# Vesta_cape.net
KiCad netlist of a schematic drawn in Altium Designer
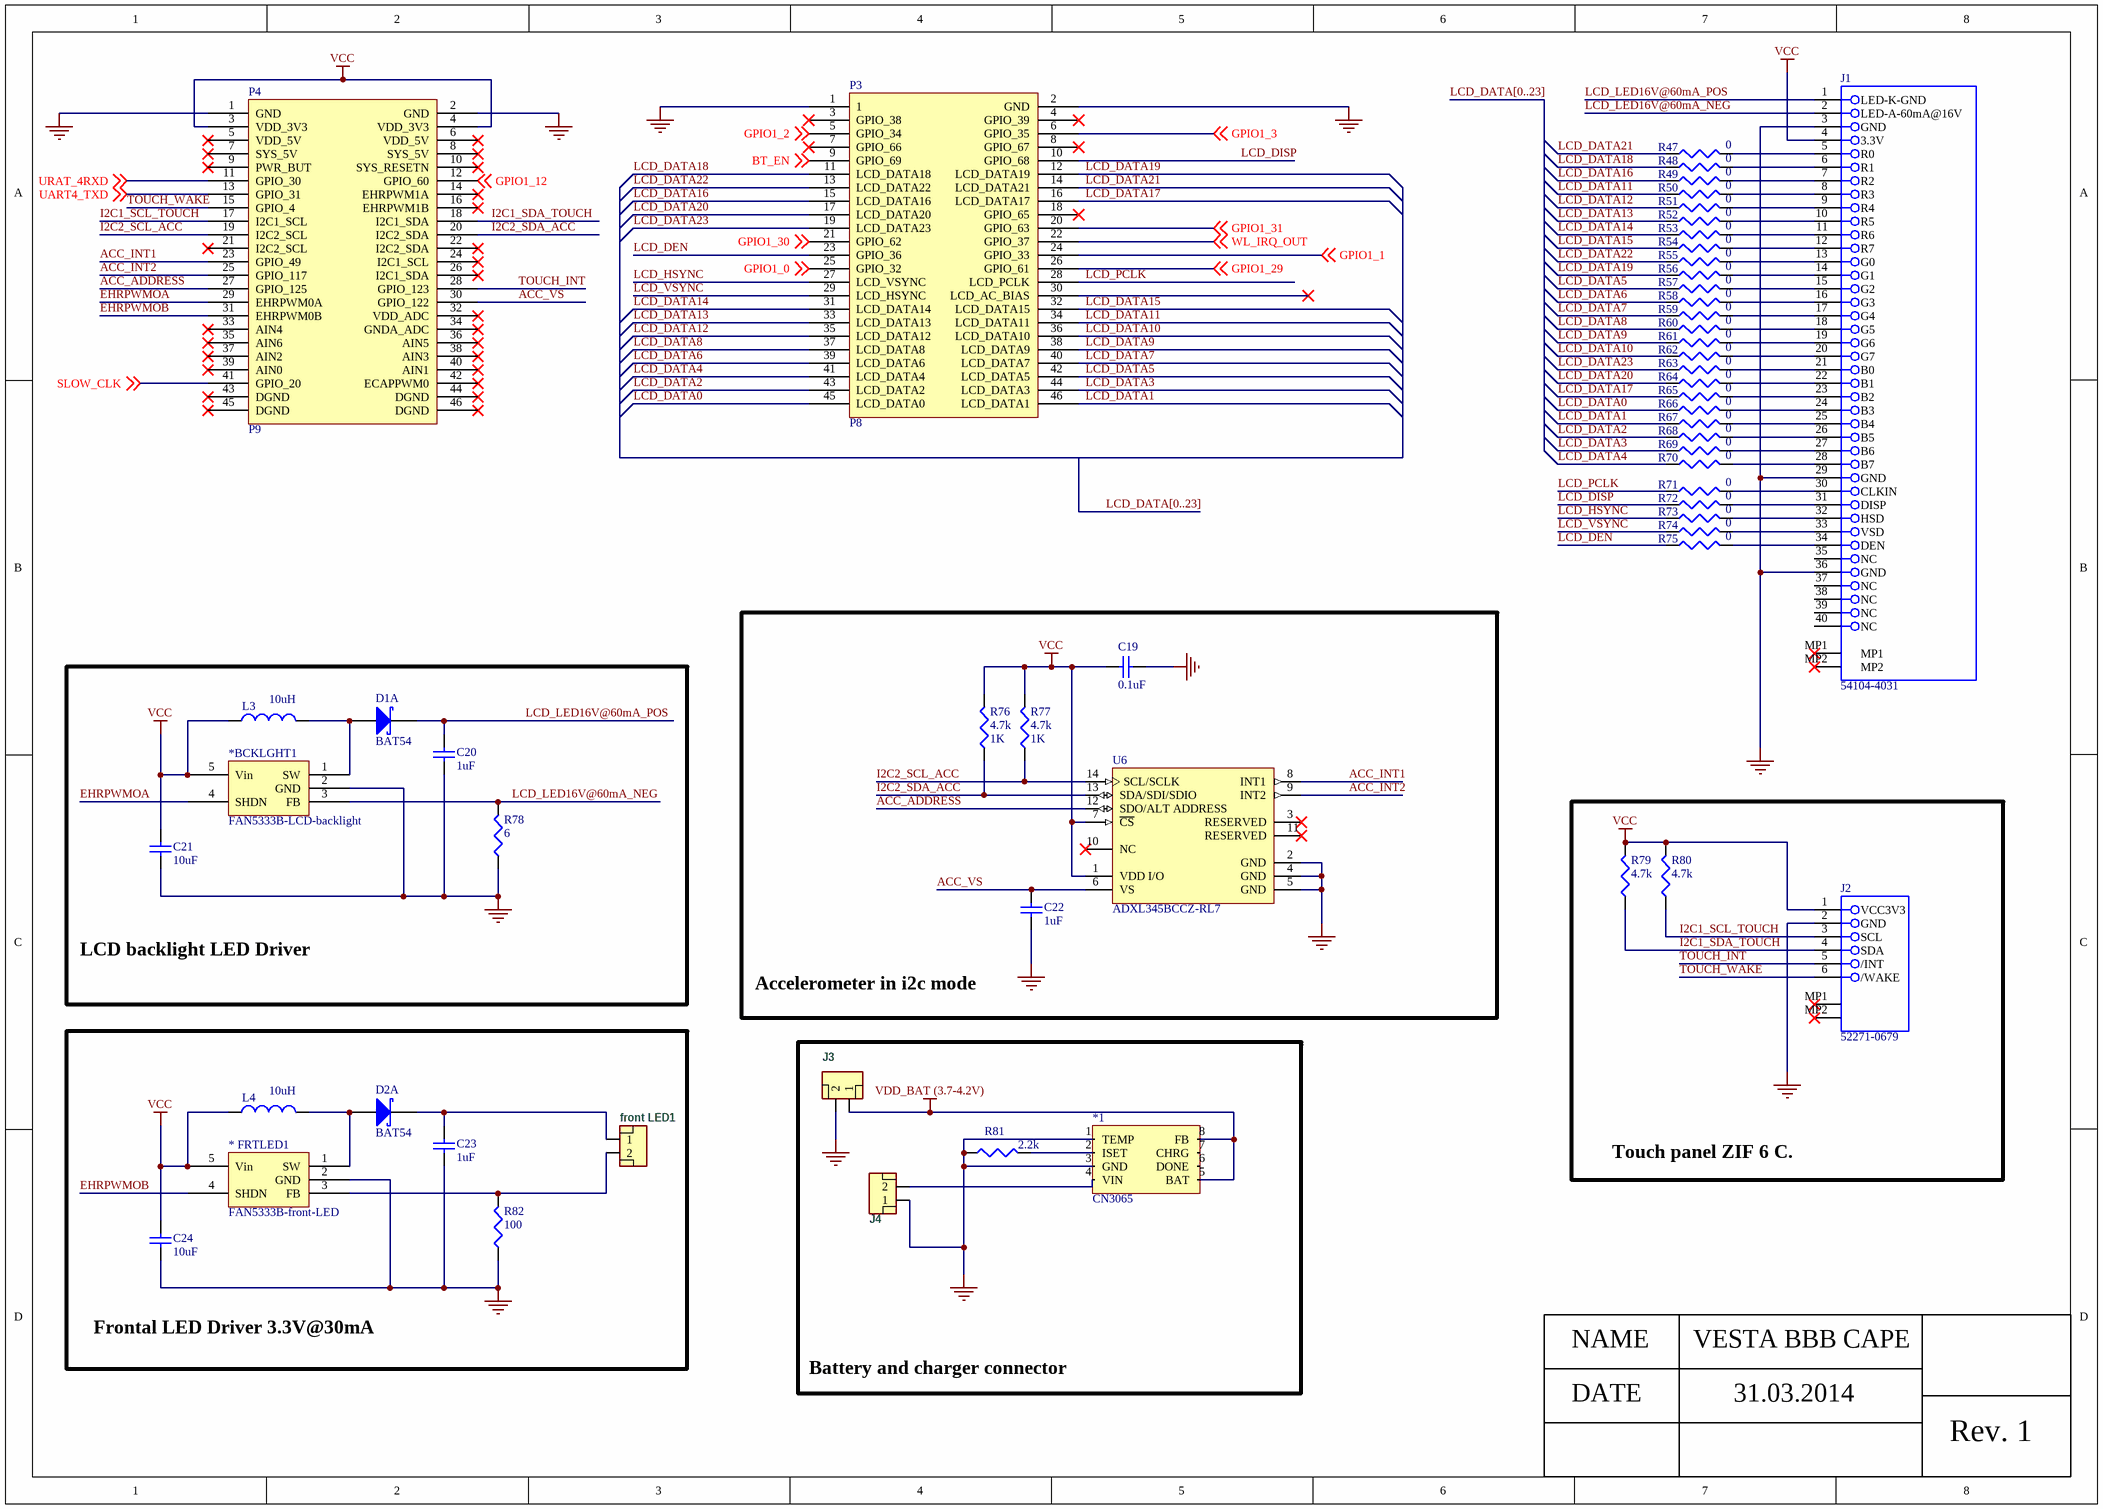
[diagram p0: Vesta_cape.SchDoc]

(export (version "E")
  (design (tool "Eeschema 10.0.6"))
  (components
    (comp (ref "* FRTLED1")
      (value "FAN5333B-front-LED")
      (footprint "FAN5333A")
      (libsource (lib "vesta_schematic_lib") (part "FAN5333B"))
    )
    (comp (ref "*1")
      (value "CN3065")
      (footprint "CN3065-LIPO")
      (libsource (lib "Vesta_cape") (part "CN3065"))
    )
    (comp (ref "*BCKLGHT1")
      (value "FAN5333B-LCD-backlight")
      (footprint "FAN5333A")
      (libsource (lib "vesta_schematic_lib") (part "FAN5333B"))
    )
    (comp (ref "C19")
      (value "0.1uF")
      (footprint "C1206")
      (description "Capacitor (Semiconductor SIM Model)")
      (fields (field (name "PUBLISHER") "Altium Limited"))
      (libsource (lib "Miscellaneous Devices") (part "Cap Semi"))
    )
    (comp (ref "C20")
      (value "1uF")
      (footprint "C1206")
      (description "Capacitor (Semiconductor SIM Model)")
      (fields (field (name "PUBLISHER") "Altium Limited"))
      (libsource (lib "Miscellaneous Devices") (part "Cap Semi"))
    )
    (comp (ref "C21")
      (value "10uF")
      (footprint "C1206")
      (description "Capacitor (Semiconductor SIM Model)")
      (fields (field (name "PUBLISHER") "Altium Limited"))
      (libsource (lib "Miscellaneous Devices") (part "Cap Semi"))
    )
    (comp (ref "C22")
      (value "1uF")
      (footprint "C1206")
      (description "Capacitor (Semiconductor SIM Model)")
      (fields (field (name "PUBLISHER") "Altium Limited"))
      (libsource (lib "Miscellaneous Devices") (part "Cap Semi"))
    )
    (comp (ref "C23")
      (value "1uF")
      (footprint "C1206")
      (description "Capacitor (Semiconductor SIM Model)")
      (fields (field (name "PUBLISHER") "Altium Limited"))
      (libsource (lib "Miscellaneous Devices") (part "Cap Semi"))
    )
    (comp (ref "C24")
      (value "10uF")
      (footprint "C1206")
      (description "Capacitor (Semiconductor SIM Model)")
      (fields (field (name "PUBLISHER") "Altium Limited"))
      (libsource (lib "Miscellaneous Devices") (part "Cap Semi"))
    )
    (comp (ref "D1")
      (value "BAT54")
      (footprint "NXP-SOT23-3_V")
      (description "Schottky Barrier Diode, 30 V, 2 uA, -55 to 150 degC, 3-Pin SOT23, RoHS, Tape and Reel")
      (fields (field (name "MANUFACTURER") "NXP Semiconductors"))
      (libsource (lib "Altium Content Vault") (part "CMP-0417-00004-1"))
    )
    (comp (ref "D2")
      (value "BAT54")
      (footprint "NXP-SOT23-3_V")
      (description "Schottky Barrier Diode, 30 V, 2 uA, -55 to 150 degC, 3-Pin SOT23, RoHS, Tape and Reel")
      (fields (field (name "MANUFACTURER") "NXP Semiconductors"))
      (libsource (lib "Altium Content Vault") (part "NXP-DSKY_A1K3-3"))
    )
    (comp (ref "front LED1")
      (value "~")
      (footprint "JMP1X2-F180_2.54")
      (description "=Description")
      (libsource (lib "") (part "JST-2_1"))
    )
    (comp (ref "J1")
      (value "54104-4031")
      (footprint "MOLX-54104-4031:MOLX-54104-4031")
      (fields (field (name "MANUFACTURER") "Molex"))
      (libsource (lib "Vesta_cape") (part "MOLX-54104-4031"))
    )
    (comp (ref "J2")
      (value "52271-0679")
      (footprint "MOLX-52271-0679:MOLX-52271-0679")
      (fields (field (name "MANUFACTURER") "Molex"))
      (libsource (lib "Vesta_cape") (part "MOLX-52271-0679"))
    )
    (comp (ref "J3")
      (value "~")
      (footprint "JMP1X2-F180_2.54")
      (description "jst2mm connector")
      (libsource (lib "") (part "JST-2_1"))
    )
    (comp (ref "J4")
      (value "~")
      (footprint "JMP1X2-F180_2.54")
      (description "jst 2mm connector")
      (libsource (lib "JST-2") (part "JST-2"))
    )
    (comp (ref "L3")
      (value "10uH")
      (footprint "0402-A")
      (description "Inductor")
      (fields (field (name "PUBLISHER") "Altium Limited"))
      (libsource (lib "Miscellaneous Devices") (part "Inductor"))
    )
    (comp (ref "L4")
      (value "10uH")
      (footprint "0402-A")
      (description "Inductor")
      (fields (field (name "PUBLISHER") "Altium Limited"))
      (libsource (lib "Miscellaneous Devices") (part "Inductor"))
    )
    (comp (ref "P3")
      (value "P8")
      (footprint "HEADER_23_2_SMD")
      (description "BBB-P8")
      (libsource (lib "Vesta_cape") (part "HDR_2_23_M_P8"))
    )
    (comp (ref "P4")
      (value "P9")
      (footprint "HEADER_23_2_SMD")
      (description "BBB-P9")
      (libsource (lib "Vesta_cape") (part "HDR2-23-M-P9"))
    )
    (comp (ref "R47")
      (value "0")
      (footprint "J1-0603")
      (description "Resistor")
      (fields (field (name "PUBLISHER") "Altium Limited"))
      (libsource (lib "Miscellaneous Devices") (part "Res3"))
    )
    (comp (ref "R48")
      (value "0")
      (footprint "J1-0603")
      (description "Resistor")
      (fields (field (name "PUBLISHER") "Altium Limited"))
      (libsource (lib "Miscellaneous Devices") (part "Res3"))
    )
    (comp (ref "R49")
      (value "0")
      (footprint "J1-0603")
      (description "Resistor")
      (fields (field (name "PUBLISHER") "Altium Limited"))
      (libsource (lib "Miscellaneous Devices") (part "Res3"))
    )
    (comp (ref "R50")
      (value "0")
      (footprint "J1-0603")
      (description "Resistor")
      (fields (field (name "PUBLISHER") "Altium Limited"))
      (libsource (lib "Miscellaneous Devices") (part "Res3"))
    )
    (comp (ref "R51")
      (value "0")
      (footprint "J1-0603")
      (description "Resistor")
      (fields (field (name "PUBLISHER") "Altium Limited"))
      (libsource (lib "Miscellaneous Devices") (part "Res3"))
    )
    (comp (ref "R52")
      (value "0")
      (footprint "J1-0603")
      (description "Resistor")
      (fields (field (name "PUBLISHER") "Altium Limited"))
      (libsource (lib "Miscellaneous Devices") (part "Res3"))
    )
    (comp (ref "R53")
      (value "0")
      (footprint "J1-0603")
      (description "Resistor")
      (fields (field (name "PUBLISHER") "Altium Limited"))
      (libsource (lib "Miscellaneous Devices") (part "Res3"))
    )
    (comp (ref "R54")
      (value "0")
      (footprint "J1-0603")
      (description "Resistor")
      (fields (field (name "PUBLISHER") "Altium Limited"))
      (libsource (lib "Miscellaneous Devices") (part "Res3"))
    )
    (comp (ref "R55")
      (value "0")
      (footprint "J1-0603")
      (description "Resistor")
      (fields (field (name "PUBLISHER") "Altium Limited"))
      (libsource (lib "Miscellaneous Devices") (part "Res3"))
    )
    (comp (ref "R56")
      (value "0")
      (footprint "J1-0603")
      (description "Resistor")
      (fields (field (name "PUBLISHER") "Altium Limited"))
      (libsource (lib "Miscellaneous Devices") (part "Res3"))
    )
    (comp (ref "R57")
      (value "0")
      (footprint "J1-0603")
      (description "Resistor")
      (fields (field (name "PUBLISHER") "Altium Limited"))
      (libsource (lib "Miscellaneous Devices") (part "Res3"))
    )
    (comp (ref "R58")
      (value "0")
      (footprint "J1-0603")
      (description "Resistor")
      (fields (field (name "PUBLISHER") "Altium Limited"))
      (libsource (lib "Miscellaneous Devices") (part "Res3"))
    )
    (comp (ref "R59")
      (value "0")
      (footprint "J1-0603")
      (description "Resistor")
      (fields (field (name "PUBLISHER") "Altium Limited"))
      (libsource (lib "Miscellaneous Devices") (part "Res3"))
    )
    (comp (ref "R60")
      (value "0")
      (footprint "J1-0603")
      (description "Resistor")
      (fields (field (name "PUBLISHER") "Altium Limited"))
      (libsource (lib "Miscellaneous Devices") (part "Res3"))
    )
    (comp (ref "R61")
      (value "0")
      (footprint "J1-0603")
      (description "Resistor")
      (fields (field (name "PUBLISHER") "Altium Limited"))
      (libsource (lib "Miscellaneous Devices") (part "Res3"))
    )
    (comp (ref "R62")
      (value "0")
      (footprint "J1-0603")
      (description "Resistor")
      (fields (field (name "PUBLISHER") "Altium Limited"))
      (libsource (lib "Miscellaneous Devices") (part "Res3"))
    )
    (comp (ref "R63")
      (value "0")
      (footprint "J1-0603")
      (description "Resistor")
      (fields (field (name "PUBLISHER") "Altium Limited"))
      (libsource (lib "Miscellaneous Devices") (part "Res3"))
    )
    (comp (ref "R64")
      (value "0")
      (footprint "J1-0603")
      (description "Resistor")
      (fields (field (name "PUBLISHER") "Altium Limited"))
      (libsource (lib "Miscellaneous Devices") (part "Res3"))
    )
    (comp (ref "R65")
      (value "0")
      (footprint "J1-0603")
      (description "Resistor")
      (fields (field (name "PUBLISHER") "Altium Limited"))
      (libsource (lib "Miscellaneous Devices") (part "Res3"))
    )
    (comp (ref "R66")
      (value "0")
      (footprint "J1-0603")
      (description "Resistor")
      (fields (field (name "PUBLISHER") "Altium Limited"))
      (libsource (lib "Miscellaneous Devices") (part "Res3"))
    )
    (comp (ref "R67")
      (value "0")
      (footprint "J1-0603")
      (description "Resistor")
      (fields (field (name "PUBLISHER") "Altium Limited"))
      (libsource (lib "Miscellaneous Devices") (part "Res3"))
    )
    (comp (ref "R68")
      (value "0")
      (footprint "J1-0603")
      (description "Resistor")
      (fields (field (name "PUBLISHER") "Altium Limited"))
      (libsource (lib "Miscellaneous Devices") (part "Res3"))
    )
    (comp (ref "R69")
      (value "0")
      (footprint "J1-0603")
      (description "Resistor")
      (fields (field (name "PUBLISHER") "Altium Limited"))
      (libsource (lib "Miscellaneous Devices") (part "Res3"))
    )
    (comp (ref "R70")
      (value "0")
      (footprint "J1-0603")
      (description "Resistor")
      (fields (field (name "PUBLISHER") "Altium Limited"))
      (libsource (lib "Miscellaneous Devices") (part "Res3"))
    )
    (comp (ref "R71")
      (value "0")
      (footprint "J1-0603")
      (description "Resistor")
      (fields (field (name "PUBLISHER") "Altium Limited"))
      (libsource (lib "Miscellaneous Devices") (part "Res3"))
    )
    (comp (ref "R72")
      (value "0")
      (footprint "J1-0603")
      (description "Resistor")
      (fields (field (name "PUBLISHER") "Altium Limited"))
      (libsource (lib "Miscellaneous Devices") (part "Res3"))
    )
    (comp (ref "R73")
      (value "0")
      (footprint "J1-0603")
      (description "Resistor")
      (fields (field (name "PUBLISHER") "Altium Limited"))
      (libsource (lib "Miscellaneous Devices") (part "Res3"))
    )
    (comp (ref "R74")
      (value "0")
      (footprint "J1-0603")
      (description "Resistor")
      (fields (field (name "PUBLISHER") "Altium Limited"))
      (libsource (lib "Miscellaneous Devices") (part "Res3"))
    )
    (comp (ref "R75")
      (value "0")
      (footprint "J1-0603")
      (description "Resistor")
      (fields (field (name "PUBLISHER") "Altium Limited"))
      (libsource (lib "Miscellaneous Devices") (part "Res3"))
    )
    (comp (ref "R76")
      (value "4.7k")
      (footprint "J1-0603")
      (description "Resistor")
      (fields (field (name "ALTIUM_VALUE") "1K") (field (name "PUBLISHER") "Altium Limited"))
      (libsource (lib "Miscellaneous Devices") (part "Res3"))
    )
    (comp (ref "R77")
      (value "4.7k")
      (footprint "J1-0603")
      (description "Resistor")
      (fields (field (name "ALTIUM_VALUE") "1K") (field (name "PUBLISHER") "Altium Limited"))
      (libsource (lib "Miscellaneous Devices") (part "Res3"))
    )
    (comp (ref "R78")
      (value "6")
      (footprint "J1-0603")
      (description "Resistor")
      (fields (field (name "PUBLISHER") "Altium Limited"))
      (libsource (lib "Miscellaneous Devices") (part "Res3"))
    )
    (comp (ref "R79")
      (value "4.7k")
      (footprint "J1-0603")
      (description "Resistor")
      (fields (field (name "PUBLISHER") "Altium Limited"))
      (libsource (lib "Miscellaneous Devices") (part "Res3"))
    )
    (comp (ref "R80")
      (value "4.7k")
      (footprint "J1-0603")
      (description "Resistor")
      (fields (field (name "PUBLISHER") "Altium Limited"))
      (libsource (lib "Miscellaneous Devices") (part "Res3"))
    )
    (comp (ref "R81")
      (value "2.2k")
      (footprint "J1-0603")
      (description "Resistor")
      (fields (field (name "PUBLISHER") "Altium Limited"))
      (libsource (lib "Miscellaneous Devices") (part "Res3"))
    )
    (comp (ref "R82")
      (value "100")
      (footprint "J1-0603")
      (description "Resistor")
      (fields (field (name "PUBLISHER") "Altium Limited"))
      (libsource (lib "Miscellaneous Devices") (part "Res3"))
    )
    (comp (ref "U6")
      (value "ADXL345BCCZ-RL7")
      (footprint "ADI-CC-14-1_V")
      (fields (field (name "MANUFACTURER") "Analog Devices"))
      (libsource (lib "Altium Content Vault") (part "ADI-ADXL34X-CC-14-1"))
    )
  )
  (nets
    (net (code "1") (name "/ACC_ADDRESS") (class "Default")
      (node (ref "P4") (pin "27") (pinfunction "GPIO_125_27") (pintype "passive"))
      (node (ref "U6") (pin "12") (pinfunction "SDO/ALT_ADDRESS_12") (pintype "bidirectional"))
    )
    (net (code "2") (name "/ACC_INT1") (class "Default")
      (node (ref "P4") (pin "23") (pinfunction "GPIO_49_23") (pintype "passive"))
      (node (ref "U6") (pin "8") (pinfunction "INT1_8") (pintype "output"))
    )
    (net (code "3") (name "/ACC_INT2") (class "Default")
      (node (ref "P4") (pin "25") (pinfunction "GPIO_117_25") (pintype "passive"))
      (node (ref "U6") (pin "9") (pinfunction "INT2_9") (pintype "output"))
    )
    (net (code "4") (name "/ACC_VS") (class "Default")
      (node (ref "C22") (pin "2") (pinfunction "2_2") (pintype "passive"))
      (node (ref "P4") (pin "30") (pinfunction "GPIO_122_30") (pintype "passive"))
      (node (ref "U6") (pin "6") (pinfunction "VS_6") (pintype "power_in"))
    )
    (net (code "5") (name "/EHRPWMOA") (class "Default")
      (node (ref "*BCKLGHT1") (pin "4") (pinfunction "SHDN_4") (pintype "passive"))
      (node (ref "P4") (pin "29") (pinfunction "EHRPWM0A_29") (pintype "passive"))
    )
    (net (code "6") (name "/EHRPWMOB") (class "Default")
      (node (ref "* FRTLED1") (pin "4") (pinfunction "SHDN_4") (pintype "passive"))
      (node (ref "P4") (pin "31") (pinfunction "EHRPWM0B_31") (pintype "passive"))
    )
    (net (code "7") (name "/I2C1_SCL_TOUCH") (class "Default")
      (node (ref "J2") (pin "3") (pinfunction "SCL_3") (pintype "passive"))
      (node (ref "P4") (pin "17") (pinfunction "I2C1_SCL_17") (pintype "passive"))
      (node (ref "R80") (pin "1") (pinfunction "1_1") (pintype "passive"))
    )
    (net (code "8") (name "/I2C1_SDA_TOUCH") (class "Default")
      (node (ref "J2") (pin "4") (pinfunction "SDA_4") (pintype "passive"))
      (node (ref "P4") (pin "18") (pinfunction "I2C1_SDA_18") (pintype "passive"))
      (node (ref "R79") (pin "1") (pinfunction "1_1") (pintype "passive"))
    )
    (net (code "9") (name "/I2C2_SCL_ACC") (class "Default")
      (node (ref "P4") (pin "19") (pinfunction "I2C2_SCL_19") (pintype "passive"))
      (node (ref "R77") (pin "1") (pinfunction "1_1") (pintype "passive"))
      (node (ref "U6") (pin "14") (pinfunction "SCL/SCLK_14") (pintype "input"))
    )
    (net (code "10") (name "/I2C2_SDA_ACC") (class "Default")
      (node (ref "P4") (pin "20") (pinfunction "I2C2_SDA_20") (pintype "passive"))
      (node (ref "R76") (pin "1") (pinfunction "1_1") (pintype "passive"))
      (node (ref "U6") (pin "13") (pinfunction "SDA/SDI/SDIO_13") (pintype "bidirectional"))
    )
    (net (code "11") (name "/LCD_DATA0") (class "Default")
      (node (ref "P3") (pin "45") (pinfunction "LCD_DATA0_45") (pintype "passive"))
      (node (ref "R66") (pin "1") (pinfunction "1_1") (pintype "passive"))
    )
    (net (code "12") (name "/LCD_DATA1") (class "Default")
      (node (ref "P3") (pin "46") (pinfunction "LCD_DATA1_46") (pintype "passive"))
      (node (ref "R67") (pin "1") (pinfunction "1_1") (pintype "passive"))
    )
    (net (code "13") (name "/LCD_DATA2") (class "Default")
      (node (ref "P3") (pin "43") (pinfunction "LCD_DATA2_43") (pintype "passive"))
      (node (ref "R68") (pin "1") (pinfunction "1_1") (pintype "passive"))
    )
    (net (code "14") (name "/LCD_DATA3") (class "Default")
      (node (ref "P3") (pin "44") (pinfunction "LCD_DATA3_44") (pintype "passive"))
      (node (ref "R69") (pin "1") (pinfunction "1_1") (pintype "passive"))
    )
    (net (code "15") (name "/LCD_DATA4") (class "Default")
      (node (ref "P3") (pin "41") (pinfunction "LCD_DATA4_41") (pintype "passive"))
      (node (ref "R70") (pin "1") (pinfunction "1_1") (pintype "passive"))
    )
    (net (code "16") (name "/LCD_DATA5") (class "Default")
      (node (ref "P3") (pin "42") (pinfunction "LCD_DATA5_42") (pintype "passive"))
      (node (ref "R57") (pin "1") (pinfunction "1_1") (pintype "passive"))
    )
    (net (code "17") (name "/LCD_DATA6") (class "Default")
      (node (ref "P3") (pin "39") (pinfunction "LCD_DATA6_39") (pintype "passive"))
      (node (ref "R58") (pin "1") (pinfunction "1_1") (pintype "passive"))
    )
    (net (code "18") (name "/LCD_DATA7") (class "Default")
      (node (ref "P3") (pin "40") (pinfunction "LCD_DATA7_40") (pintype "passive"))
      (node (ref "R59") (pin "1") (pinfunction "1_1") (pintype "passive"))
    )
    (net (code "19") (name "/LCD_DATA8") (class "Default")
      (node (ref "P3") (pin "37") (pinfunction "LCD_DATA8_37") (pintype "passive"))
      (node (ref "R60") (pin "1") (pinfunction "1_1") (pintype "passive"))
    )
    (net (code "20") (name "/LCD_DATA9") (class "Default")
      (node (ref "P3") (pin "38") (pinfunction "LCD_DATA9_38") (pintype "passive"))
      (node (ref "R61") (pin "1") (pinfunction "1_1") (pintype "passive"))
    )
    (net (code "21") (name "/LCD_DATA10") (class "Default")
      (node (ref "P3") (pin "36") (pinfunction "LCD_DATA10_36") (pintype "passive"))
      (node (ref "R62") (pin "1") (pinfunction "1_1") (pintype "passive"))
    )
    (net (code "22") (name "/LCD_DATA11") (class "Default")
      (node (ref "P3") (pin "34") (pinfunction "LCD_DATA11_34") (pintype "passive"))
      (node (ref "R50") (pin "1") (pinfunction "1_1") (pintype "passive"))
    )
    (net (code "23") (name "/LCD_DATA12") (class "Default")
      (node (ref "P3") (pin "35") (pinfunction "LCD_DATA12_35") (pintype "passive"))
      (node (ref "R51") (pin "1") (pinfunction "1_1") (pintype "passive"))
    )
    (net (code "24") (name "/LCD_DATA13") (class "Default")
      (node (ref "P3") (pin "33") (pinfunction "LCD_DATA13_33") (pintype "passive"))
      (node (ref "R52") (pin "1") (pinfunction "1_1") (pintype "passive"))
    )
    (net (code "25") (name "/LCD_DATA14") (class "Default")
      (node (ref "P3") (pin "31") (pinfunction "LCD_DATA14_31") (pintype "passive"))
      (node (ref "R53") (pin "1") (pinfunction "1_1") (pintype "passive"))
    )
    (net (code "26") (name "/LCD_DATA15") (class "Default")
      (node (ref "P3") (pin "32") (pinfunction "LCD_DATA15_32") (pintype "passive"))
      (node (ref "R54") (pin "1") (pinfunction "1_1") (pintype "passive"))
    )
    (net (code "27") (name "/LCD_DATA16") (class "Default")
      (node (ref "P3") (pin "15") (pinfunction "LCD_DATA16_15") (pintype "passive"))
      (node (ref "R49") (pin "1") (pinfunction "1_1") (pintype "passive"))
    )
    (net (code "28") (name "/LCD_DATA17") (class "Default")
      (node (ref "P3") (pin "16") (pinfunction "LCD_DATA17_16") (pintype "passive"))
      (node (ref "R65") (pin "1") (pinfunction "1_1") (pintype "passive"))
    )
    (net (code "29") (name "/LCD_DATA18") (class "Default")
      (node (ref "P3") (pin "11") (pinfunction "LCD_DATA18_11") (pintype "passive"))
      (node (ref "R48") (pin "1") (pinfunction "1_1") (pintype "passive"))
    )
    (net (code "30") (name "/LCD_DATA19") (class "Default")
      (node (ref "P3") (pin "12") (pinfunction "LCD_DATA19_12") (pintype "passive"))
      (node (ref "R56") (pin "1") (pinfunction "1_1") (pintype "passive"))
    )
    (net (code "31") (name "/LCD_DATA20") (class "Default")
      (node (ref "P3") (pin "17") (pinfunction "LCD_DATA20_17") (pintype "passive"))
      (node (ref "R64") (pin "1") (pinfunction "1_1") (pintype "passive"))
    )
    (net (code "32") (name "/LCD_DATA21") (class "Default")
      (node (ref "P3") (pin "14") (pinfunction "LCD_DATA21_14") (pintype "passive"))
      (node (ref "R47") (pin "1") (pinfunction "1_1") (pintype "passive"))
    )
    (net (code "33") (name "/LCD_DATA22") (class "Default")
      (node (ref "P3") (pin "13") (pinfunction "LCD_DATA22_13") (pintype "passive"))
      (node (ref "R55") (pin "1") (pinfunction "1_1") (pintype "passive"))
    )
    (net (code "34") (name "/LCD_DATA23") (class "Default")
      (node (ref "P3") (pin "19") (pinfunction "LCD_DATA23_19") (pintype "passive"))
      (node (ref "R63") (pin "1") (pinfunction "1_1") (pintype "passive"))
    )
    (net (code "36") (name "/LCD_DEN") (class "Default")
      (node (ref "P3") (pin "23") (pinfunction "GPIO_36_23") (pintype "passive"))
      (node (ref "R75") (pin "1") (pinfunction "1_1") (pintype "passive"))
    )
    (net (code "37") (name "/LCD_DISP") (class "Default")
      (node (ref "P3") (pin "10") (pinfunction "GPIO_68_10") (pintype "passive"))
      (node (ref "R72") (pin "1") (pinfunction "1_1") (pintype "passive"))
    )
    (net (code "38") (name "/LCD_HSYNC") (class "Default")
      (node (ref "P3") (pin "27") (pinfunction "LCD_VSYNC_27") (pintype "passive"))
      (node (ref "R73") (pin "1") (pinfunction "1_1") (pintype "passive"))
    )
    (net (code "39") (name "/LCD_LED16V@60mA_NEG") (class "Default")
      (node (ref "*BCKLGHT1") (pin "3") (pinfunction "FB_3") (pintype "passive"))
      (node (ref "J1") (pin "2") (pinfunction "LED-A-60mA@16V_2") (pintype "passive"))
      (node (ref "R78") (pin "2") (pinfunction "2_2") (pintype "passive"))
    )
    (net (code "40") (name "/LCD_LED16V@60mA_POS") (class "Default")
      (node (ref "C20") (pin "2") (pinfunction "2_2") (pintype "passive"))
      (node (ref "D1") (pin "3") (pinfunction "K_3") (pintype "passive"))
      (node (ref "J1") (pin "1") (pinfunction "LED-K-GND_1") (pintype "passive"))
    )
    (net (code "41") (name "/LCD_PCLK") (class "Default")
      (node (ref "P3") (pin "28") (pinfunction "LCD_PCLK_28") (pintype "passive"))
      (node (ref "R71") (pin "1") (pinfunction "1_1") (pintype "passive"))
    )
    (net (code "42") (name "/LCD_VSYNC") (class "Default")
      (node (ref "P3") (pin "29") (pinfunction "LCD_HSYNC_29") (pintype "passive"))
      (node (ref "R74") (pin "1") (pinfunction "1_1") (pintype "passive"))
    )
    (net (code "43") (name "/TOUCH_INT") (class "Default")
      (node (ref "J2") (pin "5") (pinfunction "/INT_5") (pintype "passive"))
      (node (ref "P4") (pin "28") (pinfunction "GPIO_123_28") (pintype "passive"))
    )
    (net (code "44") (name "/TOUCH_WAKE") (class "Default")
      (node (ref "J2") (pin "6") (pinfunction "/WAKE_6") (pintype "passive"))
      (node (ref "P4") (pin "15") (pinfunction "GPIO_4_15") (pintype "passive"))
    )
    (net (code "45") (name "BT_EN") (class "Default")
      (node (ref "P3") (pin "9") (pinfunction "GPIO_69_9") (pintype "passive"))
    )
    (net (code "46") (name "GND") (class "Default")
      (node (ref "* FRTLED1") (pin "2") (pinfunction "GND_2") (pintype "passive"))
      (node (ref "*1") (pin "1") (pinfunction "TEMP_1") (pintype "passive"))
      (node (ref "*1") (pin "3") (pinfunction "GND_3") (pintype "passive"))
      (node (ref "*BCKLGHT1") (pin "2") (pinfunction "GND_2") (pintype "passive"))
      (node (ref "C19") (pin "1") (pinfunction "1_1") (pintype "passive"))
      (node (ref "C20") (pin "1") (pinfunction "1_1") (pintype "passive"))
      (node (ref "C21") (pin "1") (pinfunction "1_1") (pintype "passive"))
      (node (ref "C22") (pin "1") (pinfunction "1_1") (pintype "passive"))
      (node (ref "C23") (pin "1") (pinfunction "1_1") (pintype "passive"))
      (node (ref "C24") (pin "1") (pinfunction "1_1") (pintype "passive"))
      (node (ref "J1") (pin "29") (pinfunction "GND_29") (pintype "passive"))
      (node (ref "J1") (pin "3") (pinfunction "GND_3") (pintype "passive"))
      (node (ref "J1") (pin "36") (pinfunction "GND_36") (pintype "passive"))
      (node (ref "J2") (pin "2") (pinfunction "GND_2") (pintype "passive"))
      (node (ref "J3") (pin "2") (pinfunction "2_2") (pintype "passive"))
      (node (ref "J4") (pin "1") (pinfunction "1_1") (pintype "passive"))
      (node (ref "P3") (pin "1") (pinfunction "1_1") (pintype "passive"))
      (node (ref "P3") (pin "2") (pinfunction "GND_2") (pintype "passive"))
      (node (ref "P4") (pin "1") (pinfunction "GND_1") (pintype "passive"))
      (node (ref "P4") (pin "2") (pinfunction "GND_2") (pintype "passive"))
      (node (ref "R78") (pin "1") (pinfunction "1_1") (pintype "passive"))
      (node (ref "R81") (pin "1") (pinfunction "1_1") (pintype "passive"))
      (node (ref "R82") (pin "1") (pinfunction "1_1") (pintype "passive"))
      (node (ref "U6") (pin "2") (pinfunction "GND_2") (pintype "power_in"))
      (node (ref "U6") (pin "4") (pinfunction "GND_4") (pintype "power_in"))
      (node (ref "U6") (pin "5") (pinfunction "GND_5") (pintype "power_in"))
    )
    (net (code "47") (name "GPIO1_0") (class "Default")
      (node (ref "P3") (pin "25") (pinfunction "GPIO_32_25") (pintype "passive"))
    )
    (net (code "48") (name "GPIO1_1") (class "Default")
      (node (ref "P3") (pin "24") (pinfunction "GPIO_33_24") (pintype "passive"))
    )
    (net (code "49") (name "GPIO1_2") (class "Default")
      (node (ref "P3") (pin "5") (pinfunction "GPIO_34_5") (pintype "passive"))
    )
    (net (code "50") (name "GPIO1_3") (class "Default")
      (node (ref "P3") (pin "6") (pinfunction "GPIO_35_6") (pintype "passive"))
    )
    (net (code "51") (name "GPIO1_12") (class "Default")
      (node (ref "P4") (pin "12") (pinfunction "GPIO_60_12") (pintype "passive"))
    )
    (net (code "52") (name "GPIO1_29") (class "Default")
      (node (ref "P3") (pin "26") (pinfunction "GPIO_61_26") (pintype "passive"))
    )
    (net (code "53") (name "GPIO1_30") (class "Default")
      (node (ref "P3") (pin "21") (pinfunction "GPIO_62_21") (pintype "passive"))
    )
    (net (code "54") (name "GPIO1_31") (class "Default")
      (node (ref "P3") (pin "20") (pinfunction "GPIO_63_20") (pintype "passive"))
    )
    (net (code "55") (name "Net-(* FRTLED1-FB)") (class "Default")
      (node (ref "* FRTLED1") (pin "3") (pinfunction "FB_3") (pintype "passive"))
      (node (ref "R82") (pin "2") (pinfunction "2_2") (pintype "passive"))
      (node (ref "front LED1") (pin "2") (pinfunction "2_2") (pintype "passive"))
    )
    (net (code "56") (name "Net-(* FRTLED1-SW)") (class "Default")
      (node (ref "* FRTLED1") (pin "1") (pinfunction "SW_1") (pintype "passive"))
      (node (ref "D2") (pin "1") (pinfunction "A_1") (pintype "passive"))
      (node (ref "L4") (pin "2") (pinfunction "2_2") (pintype "passive"))
    )
    (net (code "57") (name "Net-(*1-ISET)") (class "Default")
      (node (ref "*1") (pin "2") (pinfunction "ISET_2") (pintype "passive"))
      (node (ref "R81") (pin "2") (pinfunction "2_2") (pintype "passive"))
    )
    (net (code "58") (name "Net-(*1-VIN)") (class "Default")
      (node (ref "*1") (pin "4") (pinfunction "VIN_4") (pintype "passive"))
      (node (ref "J4") (pin "2") (pinfunction "2_2") (pintype "passive"))
    )
    (net (code "59") (name "Net-(*BCKLGHT1-SW)") (class "Default")
      (node (ref "*BCKLGHT1") (pin "1") (pinfunction "SW_1") (pintype "passive"))
      (node (ref "D1") (pin "1") (pinfunction "A_1") (pintype "passive"))
      (node (ref "L3") (pin "2") (pinfunction "2_2") (pintype "passive"))
    )
    (net (code "60") (name "Net-(D2A-K)") (class "Default")
      (node (ref "C23") (pin "2") (pinfunction "2_2") (pintype "passive"))
      (node (ref "D2") (pin "3") (pinfunction "K_3") (pintype "passive"))
      (node (ref "front LED1") (pin "1") (pinfunction "1_1") (pintype "passive"))
    )
    (net (code "61") (name "Net-(J1-B0)") (class "Default")
      (node (ref "J1") (pin "21") (pinfunction "B0_21") (pintype "passive"))
      (node (ref "R63") (pin "2") (pinfunction "2_2") (pintype "passive"))
    )
    (net (code "62") (name "Net-(J1-B1)") (class "Default")
      (node (ref "J1") (pin "22") (pinfunction "B1_22") (pintype "passive"))
      (node (ref "R64") (pin "2") (pinfunction "2_2") (pintype "passive"))
    )
    (net (code "63") (name "Net-(J1-B2)") (class "Default")
      (node (ref "J1") (pin "23") (pinfunction "B2_23") (pintype "passive"))
      (node (ref "R65") (pin "2") (pinfunction "2_2") (pintype "passive"))
    )
    (net (code "64") (name "Net-(J1-B3)") (class "Default")
      (node (ref "J1") (pin "24") (pinfunction "B3_24") (pintype "passive"))
      (node (ref "R66") (pin "2") (pinfunction "2_2") (pintype "passive"))
    )
    (net (code "65") (name "Net-(J1-B4)") (class "Default")
      (node (ref "J1") (pin "25") (pinfunction "B4_25") (pintype "passive"))
      (node (ref "R67") (pin "2") (pinfunction "2_2") (pintype "passive"))
    )
    (net (code "66") (name "Net-(J1-B5)") (class "Default")
      (node (ref "J1") (pin "26") (pinfunction "B5_26") (pintype "passive"))
      (node (ref "R68") (pin "2") (pinfunction "2_2") (pintype "passive"))
    )
    (net (code "67") (name "Net-(J1-B6)") (class "Default")
      (node (ref "J1") (pin "27") (pinfunction "B6_27") (pintype "passive"))
      (node (ref "R69") (pin "2") (pinfunction "2_2") (pintype "passive"))
    )
    (net (code "68") (name "Net-(J1-B7)") (class "Default")
      (node (ref "J1") (pin "28") (pinfunction "B7_28") (pintype "passive"))
      (node (ref "R70") (pin "2") (pinfunction "2_2") (pintype "passive"))
    )
    (net (code "69") (name "Net-(J1-CLKIN)") (class "Default")
      (node (ref "J1") (pin "30") (pinfunction "CLKIN_30") (pintype "passive"))
      (node (ref "R71") (pin "2") (pinfunction "2_2") (pintype "passive"))
    )
    (net (code "70") (name "Net-(J1-DEN)") (class "Default")
      (node (ref "J1") (pin "34") (pinfunction "DEN_34") (pintype "passive"))
      (node (ref "R75") (pin "2") (pinfunction "2_2") (pintype "passive"))
    )
    (net (code "71") (name "Net-(J1-DISP)") (class "Default")
      (node (ref "J1") (pin "31") (pinfunction "DISP_31") (pintype "passive"))
      (node (ref "R72") (pin "2") (pinfunction "2_2") (pintype "passive"))
    )
    (net (code "72") (name "Net-(J1-G0)") (class "Default")
      (node (ref "J1") (pin "13") (pinfunction "G0_13") (pintype "passive"))
      (node (ref "R55") (pin "2") (pinfunction "2_2") (pintype "passive"))
    )
    (net (code "73") (name "Net-(J1-G1)") (class "Default")
      (node (ref "J1") (pin "14") (pinfunction "G1_14") (pintype "passive"))
      (node (ref "R56") (pin "2") (pinfunction "2_2") (pintype "passive"))
    )
    (net (code "74") (name "Net-(J1-G2)") (class "Default")
      (node (ref "J1") (pin "15") (pinfunction "G2_15") (pintype "passive"))
      (node (ref "R57") (pin "2") (pinfunction "2_2") (pintype "passive"))
    )
    (net (code "75") (name "Net-(J1-G3)") (class "Default")
      (node (ref "J1") (pin "16") (pinfunction "G3_16") (pintype "passive"))
      (node (ref "R58") (pin "2") (pinfunction "2_2") (pintype "passive"))
    )
    (net (code "76") (name "Net-(J1-G4)") (class "Default")
      (node (ref "J1") (pin "17") (pinfunction "G4_17") (pintype "passive"))
      (node (ref "R59") (pin "2") (pinfunction "2_2") (pintype "passive"))
    )
    (net (code "77") (name "Net-(J1-G5)") (class "Default")
      (node (ref "J1") (pin "18") (pinfunction "G5_18") (pintype "passive"))
      (node (ref "R60") (pin "2") (pinfunction "2_2") (pintype "passive"))
    )
    (net (code "78") (name "Net-(J1-G6)") (class "Default")
      (node (ref "J1") (pin "19") (pinfunction "G6_19") (pintype "passive"))
      (node (ref "R61") (pin "2") (pinfunction "2_2") (pintype "passive"))
    )
    (net (code "79") (name "Net-(J1-G7)") (class "Default")
      (node (ref "J1") (pin "20") (pinfunction "G7_20") (pintype "passive"))
      (node (ref "R62") (pin "2") (pinfunction "2_2") (pintype "passive"))
    )
    (net (code "80") (name "Net-(J1-HSD)") (class "Default")
      (node (ref "J1") (pin "32") (pinfunction "HSD_32") (pintype "passive"))
      (node (ref "R73") (pin "2") (pinfunction "2_2") (pintype "passive"))
    )
    (net (code "81") (name "Net-(J1-R0)") (class "Default")
      (node (ref "J1") (pin "5") (pinfunction "R0_5") (pintype "passive"))
      (node (ref "R47") (pin "2") (pinfunction "2_2") (pintype "passive"))
    )
    (net (code "82") (name "Net-(J1-R1)") (class "Default")
      (node (ref "J1") (pin "6") (pinfunction "R1_6") (pintype "passive"))
      (node (ref "R48") (pin "2") (pinfunction "2_2") (pintype "passive"))
    )
    (net (code "83") (name "Net-(J1-R2)") (class "Default")
      (node (ref "J1") (pin "7") (pinfunction "R2_7") (pintype "passive"))
      (node (ref "R49") (pin "2") (pinfunction "2_2") (pintype "passive"))
    )
    (net (code "84") (name "Net-(J1-R3)") (class "Default")
      (node (ref "J1") (pin "8") (pinfunction "R3_8") (pintype "passive"))
      (node (ref "R50") (pin "2") (pinfunction "2_2") (pintype "passive"))
    )
    (net (code "85") (name "Net-(J1-R4)") (class "Default")
      (node (ref "J1") (pin "9") (pinfunction "R4_9") (pintype "passive"))
      (node (ref "R51") (pin "2") (pinfunction "2_2") (pintype "passive"))
    )
    (net (code "86") (name "Net-(J1-R5)") (class "Default")
      (node (ref "J1") (pin "10") (pinfunction "R5_10") (pintype "passive"))
      (node (ref "R52") (pin "2") (pinfunction "2_2") (pintype "passive"))
    )
    (net (code "87") (name "Net-(J1-R6)") (class "Default")
      (node (ref "J1") (pin "11") (pinfunction "R6_11") (pintype "passive"))
      (node (ref "R53") (pin "2") (pinfunction "2_2") (pintype "passive"))
    )
    (net (code "88") (name "Net-(J1-R7)") (class "Default")
      (node (ref "J1") (pin "12") (pinfunction "R7_12") (pintype "passive"))
      (node (ref "R54") (pin "2") (pinfunction "2_2") (pintype "passive"))
    )
    (net (code "89") (name "Net-(J1-VSD)") (class "Default")
      (node (ref "J1") (pin "33") (pinfunction "VSD_33") (pintype "passive"))
      (node (ref "R74") (pin "2") (pinfunction "2_2") (pintype "passive"))
    )
    (net (code "90") (name "SLOW_CLK") (class "Default")
      (node (ref "P4") (pin "41") (pinfunction "GPIO_20_41") (pintype "passive"))
    )
    (net (code "91") (name "UART4_TXD") (class "Default")
      (node (ref "P4") (pin "13") (pinfunction "GPIO_31_13") (pintype "passive"))
    )
    (net (code "92") (name "URAT_4RXD") (class "Default")
      (node (ref "P4") (pin "11") (pinfunction "GPIO_30_11") (pintype "passive"))
    )
    (net (code "93") (name "VCC") (class "Default")
      (node (ref "* FRTLED1") (pin "5") (pinfunction "Vin_5") (pintype "passive"))
      (node (ref "*BCKLGHT1") (pin "5") (pinfunction "Vin_5") (pintype "passive"))
      (node (ref "C19") (pin "2") (pinfunction "2_2") (pintype "passive"))
      (node (ref "C21") (pin "2") (pinfunction "2_2") (pintype "passive"))
      (node (ref "C24") (pin "2") (pinfunction "2_2") (pintype "passive"))
      (node (ref "J1") (pin "4") (pinfunction "3.3V_4") (pintype "passive"))
      (node (ref "J2") (pin "1") (pinfunction "VCC3V3_1") (pintype "passive"))
      (node (ref "L3") (pin "1") (pinfunction "1_1") (pintype "passive"))
      (node (ref "L4") (pin "1") (pinfunction "1_1") (pintype "passive"))
      (node (ref "P4") (pin "3") (pinfunction "VDD_3V3_3") (pintype "passive"))
      (node (ref "P4") (pin "4") (pinfunction "VDD_3V3_4") (pintype "passive"))
      (node (ref "R76") (pin "2") (pinfunction "2_2") (pintype "passive"))
      (node (ref "R77") (pin "2") (pinfunction "2_2") (pintype "passive"))
      (node (ref "R79") (pin "2") (pinfunction "2_2") (pintype "passive"))
      (node (ref "R80") (pin "2") (pinfunction "2_2") (pintype "passive"))
      (node (ref "U6") (pin "1") (pinfunction "VDD_I/O_1") (pintype "power_in"))
      (node (ref "U6") (pin "7") (pinfunction "~{CS}_7") (pintype "input"))
    )
    (net (code "94") (name "VDD_BAT (3.7-4.2V)") (class "Default")
      (node (ref "*1") (pin "5") (pinfunction "BAT_5") (pintype "passive"))
      (node (ref "*1") (pin "8") (pinfunction "FB_8") (pintype "passive"))
      (node (ref "J3") (pin "1") (pinfunction "1_1") (pintype "passive"))
    )
    (net (code "95") (name "WL_IRQ_OUT") (class "Default")
      (node (ref "P3") (pin "22") (pinfunction "GPIO_37_22") (pintype "passive"))
    )
    (net (code "96") (name "unconnected-(*1-CHRG-Pad7)") (class "Default")
      (node (ref "*1") (pin "7") (pinfunction "CHRG_7") (pintype "passive"))
    )
    (net (code "97") (name "unconnected-(*1-DONE-Pad6)") (class "Default")
      (node (ref "*1") (pin "6") (pinfunction "DONE_6") (pintype "passive"))
    )
    (net (code "98") (name "unconnected-(J1-NC-Pad35)") (class "Default")
      (node (ref "J1") (pin "35") (pinfunction "NC_35") (pintype "passive"))
    )
    (net (code "99") (name "unconnected-(J1-NC-Pad37)") (class "Default")
      (node (ref "J1") (pin "37") (pinfunction "NC_37") (pintype "passive"))
    )
    (net (code "100") (name "unconnected-(J1-NC-Pad38)") (class "Default")
      (node (ref "J1") (pin "38") (pinfunction "NC_38") (pintype "passive"))
    )
    (net (code "101") (name "unconnected-(J1-NC-Pad39)") (class "Default")
      (node (ref "J1") (pin "39") (pinfunction "NC_39") (pintype "passive"))
    )
    (net (code "102") (name "unconnected-(J1-NC-Pad40)") (class "Default")
      (node (ref "J1") (pin "40") (pinfunction "NC_40") (pintype "passive"))
    )
    (net (code "103") (name "unconnected-(J1-PadMP1)") (class "Default")
      (node (ref "J1") (pin "MP1") (pinfunction "MP1_MP1") (pintype "passive+no_connect"))
    )
    (net (code "104") (name "unconnected-(J1-PadMP2)") (class "Default")
      (node (ref "J1") (pin "MP2") (pinfunction "MP2_MP2") (pintype "passive+no_connect"))
    )
    (net (code "105") (name "unconnected-(J2-PadMP1)") (class "Default")
      (node (ref "J2") (pin "MP1") (pinfunction "MP1_MP1") (pintype "passive+no_connect"))
    )
    (net (code "106") (name "unconnected-(J2-PadMP2)") (class "Default")
      (node (ref "J2") (pin "MP2") (pinfunction "MP2_MP2") (pintype "passive+no_connect"))
    )
    (net (code "107") (name "unconnected-(P3-GPIO_38-Pad3)") (class "Default")
      (node (ref "P3") (pin "3") (pinfunction "GPIO_38_3") (pintype "passive+no_connect"))
    )
    (net (code "108") (name "unconnected-(P3-GPIO_39-Pad4)") (class "Default")
      (node (ref "P3") (pin "4") (pinfunction "GPIO_39_4") (pintype "passive+no_connect"))
    )
    (net (code "109") (name "unconnected-(P3-GPIO_65-Pad18)") (class "Default")
      (node (ref "P3") (pin "18") (pinfunction "GPIO_65_18") (pintype "passive+no_connect"))
    )
    (net (code "110") (name "unconnected-(P3-GPIO_66-Pad7)") (class "Default")
      (node (ref "P3") (pin "7") (pinfunction "GPIO_66_7") (pintype "passive+no_connect"))
    )
    (net (code "111") (name "unconnected-(P3-GPIO_67-Pad8)") (class "Default")
      (node (ref "P3") (pin "8") (pinfunction "GPIO_67_8") (pintype "passive+no_connect"))
    )
    (net (code "112") (name "unconnected-(P3-LCD_AC_BIAS-Pad30)") (class "Default")
      (node (ref "P3") (pin "30") (pinfunction "LCD_AC_BIAS_30") (pintype "passive+no_connect"))
    )
    (net (code "113") (name "unconnected-(P4-AIN0-Pad39)") (class "Default")
      (node (ref "P4") (pin "39") (pinfunction "AIN0_39") (pintype "passive+no_connect"))
    )
    (net (code "114") (name "unconnected-(P4-AIN1-Pad40)") (class "Default")
      (node (ref "P4") (pin "40") (pinfunction "AIN1_40") (pintype "passive+no_connect"))
    )
    (net (code "115") (name "unconnected-(P4-AIN2-Pad37)") (class "Default")
      (node (ref "P4") (pin "37") (pinfunction "AIN2_37") (pintype "passive+no_connect"))
    )
    (net (code "116") (name "unconnected-(P4-AIN3-Pad38)") (class "Default")
      (node (ref "P4") (pin "38") (pinfunction "AIN3_38") (pintype "passive+no_connect"))
    )
    (net (code "117") (name "unconnected-(P4-AIN4-Pad33)") (class "Default")
      (node (ref "P4") (pin "33") (pinfunction "AIN4_33") (pintype "passive+no_connect"))
    )
    (net (code "118") (name "unconnected-(P4-AIN5-Pad36)") (class "Default")
      (node (ref "P4") (pin "36") (pinfunction "AIN5_36") (pintype "passive+no_connect"))
    )
    (net (code "119") (name "unconnected-(P4-AIN6-Pad35)") (class "Default")
      (node (ref "P4") (pin "35") (pinfunction "AIN6_35") (pintype "passive+no_connect"))
    )
    (net (code "120") (name "unconnected-(P4-DGND-Pad43)") (class "Default")
      (node (ref "P4") (pin "43") (pinfunction "DGND_43") (pintype "passive+no_connect"))
    )
    (net (code "121") (name "unconnected-(P4-DGND-Pad44)") (class "Default")
      (node (ref "P4") (pin "44") (pinfunction "DGND_44") (pintype "passive+no_connect"))
    )
    (net (code "122") (name "unconnected-(P4-DGND-Pad45)") (class "Default")
      (node (ref "P4") (pin "45") (pinfunction "DGND_45") (pintype "passive+no_connect"))
    )
    (net (code "123") (name "unconnected-(P4-DGND-Pad46)") (class "Default")
      (node (ref "P4") (pin "46") (pinfunction "DGND_46") (pintype "passive+no_connect"))
    )
    (net (code "124") (name "unconnected-(P4-ECAPPWM0-Pad42)") (class "Default")
      (node (ref "P4") (pin "42") (pinfunction "ECAPPWM0_42") (pintype "passive+no_connect"))
    )
    (net (code "125") (name "unconnected-(P4-EHRPWM1A-Pad14)") (class "Default")
      (node (ref "P4") (pin "14") (pinfunction "EHRPWM1A_14") (pintype "passive+no_connect"))
    )
    (net (code "126") (name "unconnected-(P4-EHRPWM1B-Pad16)") (class "Default")
      (node (ref "P4") (pin "16") (pinfunction "EHRPWM1B_16") (pintype "passive+no_connect"))
    )
    (net (code "127") (name "unconnected-(P4-GNDA_ADC-Pad34)") (class "Default")
      (node (ref "P4") (pin "34") (pinfunction "GNDA_ADC_34") (pintype "passive+no_connect"))
    )
    (net (code "128") (name "unconnected-(P4-I2C1_SCL-Pad24)") (class "Default")
      (node (ref "P4") (pin "24") (pinfunction "I2C1_SCL_24") (pintype "passive+no_connect"))
    )
    (net (code "129") (name "unconnected-(P4-I2C1_SDA-Pad26)") (class "Default")
      (node (ref "P4") (pin "26") (pinfunction "I2C1_SDA_26") (pintype "passive+no_connect"))
    )
    (net (code "130") (name "unconnected-(P4-I2C2_SCL-Pad21)") (class "Default")
      (node (ref "P4") (pin "21") (pinfunction "I2C2_SCL_21") (pintype "passive+no_connect"))
    )
    (net (code "131") (name "unconnected-(P4-I2C2_SDA-Pad22)") (class "Default")
      (node (ref "P4") (pin "22") (pinfunction "I2C2_SDA_22") (pintype "passive+no_connect"))
    )
    (net (code "132") (name "unconnected-(P4-PWR_BUT-Pad9)") (class "Default")
      (node (ref "P4") (pin "9") (pinfunction "PWR_BUT_9") (pintype "passive+no_connect"))
    )
    (net (code "133") (name "unconnected-(P4-SYS_5V-Pad7)") (class "Default")
      (node (ref "P4") (pin "7") (pinfunction "SYS_5V_7") (pintype "passive+no_connect"))
    )
    (net (code "134") (name "unconnected-(P4-SYS_5V-Pad8)") (class "Default")
      (node (ref "P4") (pin "8") (pinfunction "SYS_5V_8") (pintype "passive+no_connect"))
    )
    (net (code "135") (name "unconnected-(P4-SYS_RESETN-Pad10)") (class "Default")
      (node (ref "P4") (pin "10") (pinfunction "SYS_RESETN_10") (pintype "passive+no_connect"))
    )
    (net (code "136") (name "unconnected-(P4-VDD_5V-Pad5)") (class "Default")
      (node (ref "P4") (pin "5") (pinfunction "VDD_5V_5") (pintype "passive+no_connect"))
    )
    (net (code "137") (name "unconnected-(P4-VDD_5V-Pad6)") (class "Default")
      (node (ref "P4") (pin "6") (pinfunction "VDD_5V_6") (pintype "passive+no_connect"))
    )
    (net (code "138") (name "unconnected-(P4-VDD_ADC-Pad32)") (class "Default")
      (node (ref "P4") (pin "32") (pinfunction "VDD_ADC_32") (pintype "passive+no_connect"))
    )
    (net (code "139") (name "unconnected-(U6-NC-Pad10)") (class "Default")
      (node (ref "U6") (pin "10") (pinfunction "NC_10") (pintype "passive+no_connect"))
    )
    (net (code "140") (name "unconnected-(U6-RESERVED-Pad3)") (class "Default")
      (node (ref "U6") (pin "3") (pinfunction "RESERVED_3") (pintype "passive+no_connect"))
    )
    (net (code "141") (name "unconnected-(U6-RESERVED-Pad11)") (class "Default")
      (node (ref "U6") (pin "11") (pinfunction "RESERVED_11") (pintype "passive+no_connect"))
    )
  )
)
